# DURST_VT4_V0_3.net
KiCad netlist of a schematic drawn in EAGLE
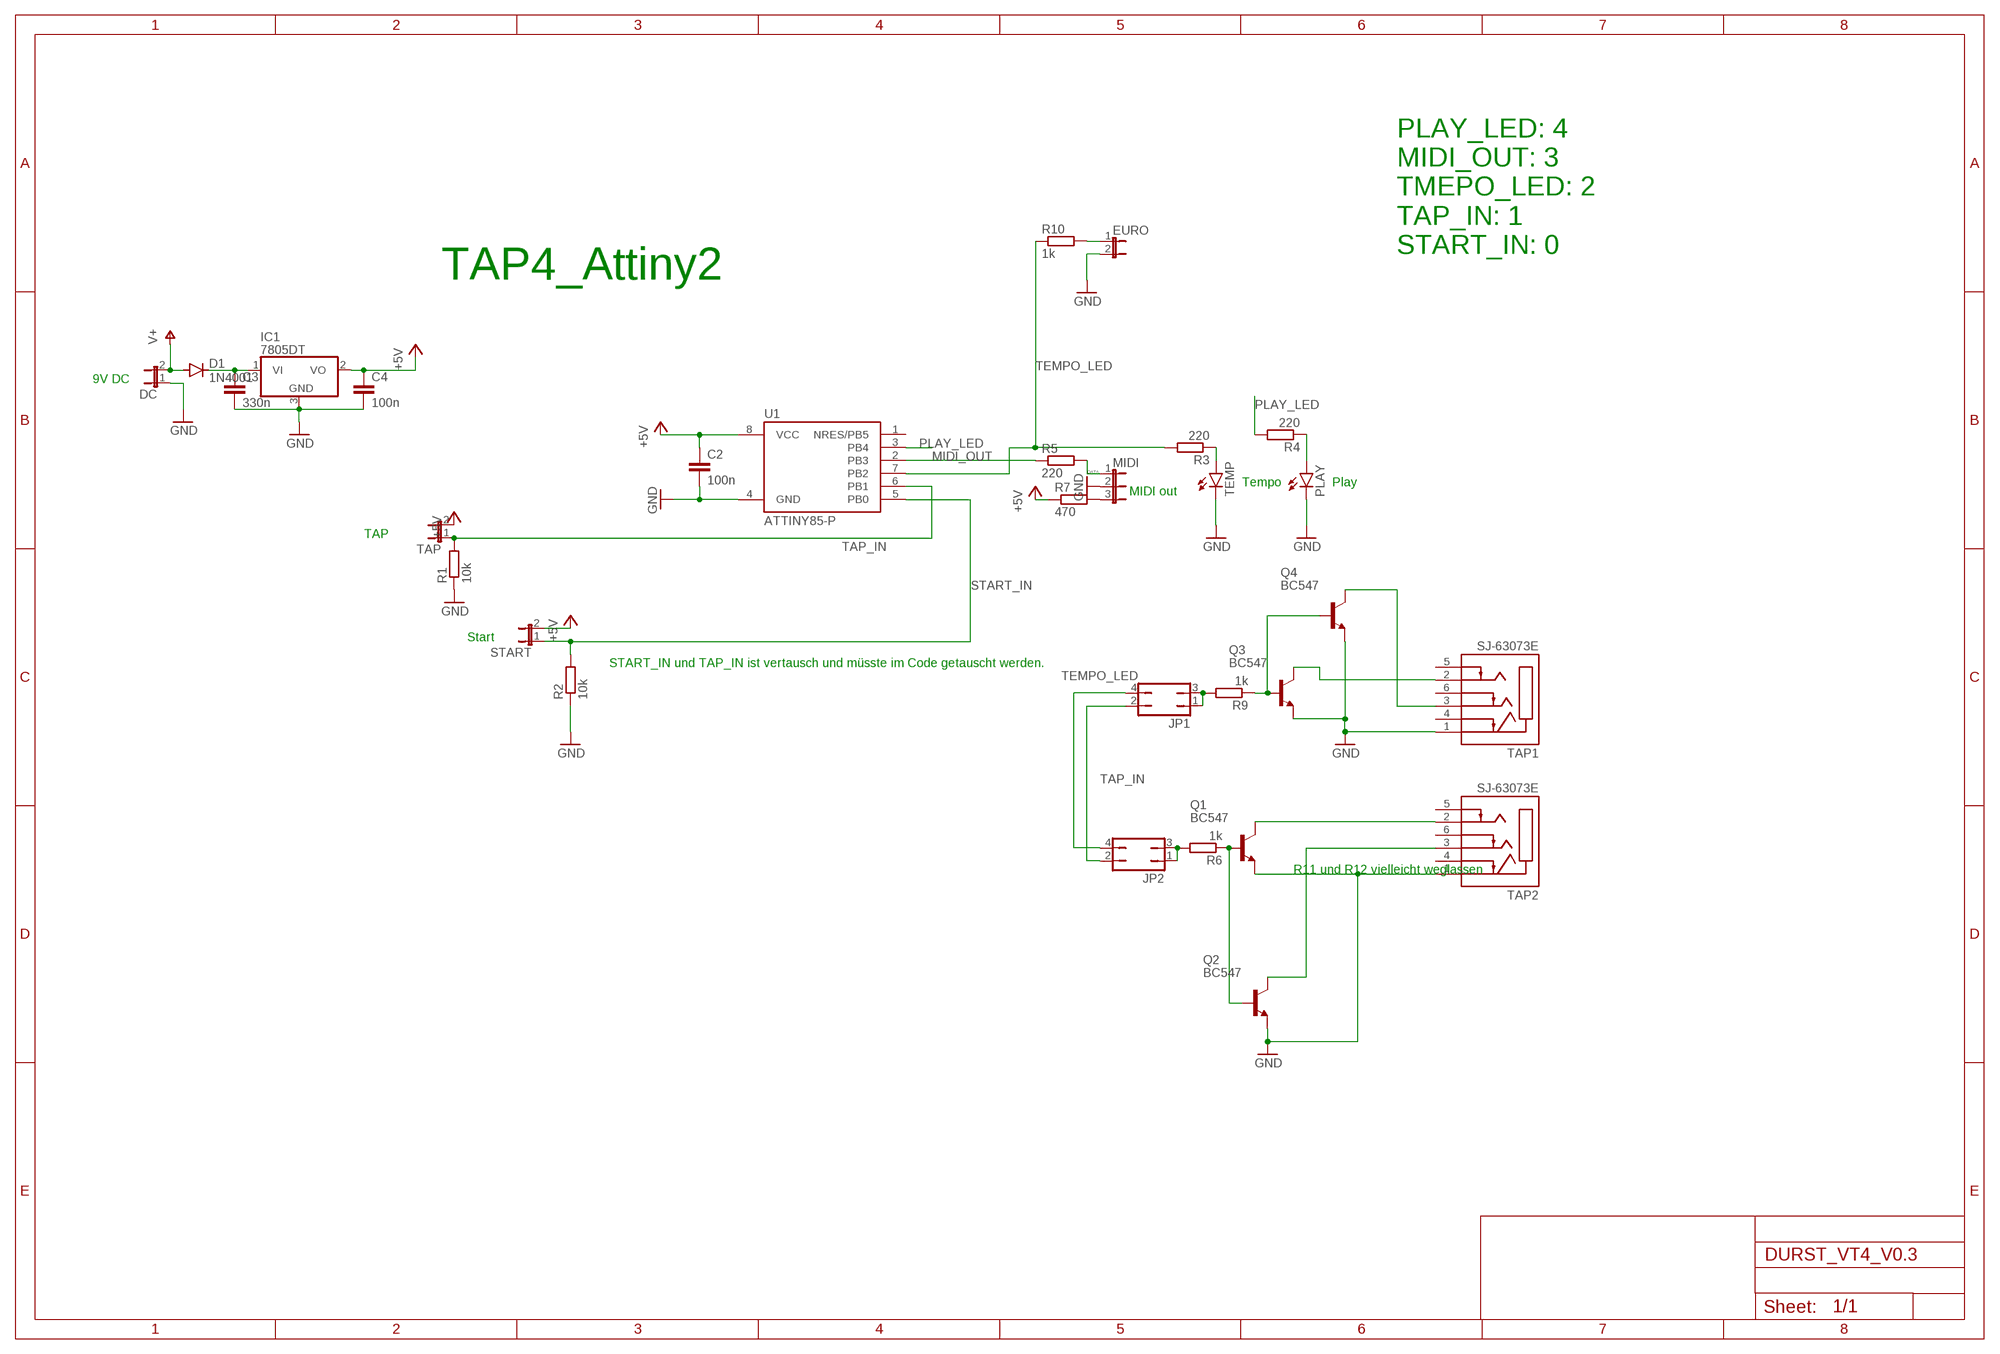
[diagram p0: schematic, sheet 1]

(export (version "E")
  (design (tool "Eeschema 10.0.6"))
  (components
    (comp (ref "C2")
      (value "100n")
      (footprint "eagle-import:C050-024X044")
      (libsource (lib "eagle-import") (part "C-EU050-024X044"))
    )
    (comp (ref "C3")
      (value "330n")
      (footprint "eagle-import:C025-024X044")
      (libsource (lib "eagle-import") (part "C-EU025-024X044"))
    )
    (comp (ref "C4")
      (value "100n")
      (footprint "eagle-import:C025-024X044")
      (libsource (lib "eagle-import") (part "C-EU025-024X044"))
    )
    (comp (ref "D1")
      (value "1N4001")
      (footprint "eagle-import:DO41-10")
      (libsource (lib "eagle-import") (part "1N4004"))
    )
    (comp (ref "DC")
      (value "JP1E")
      (footprint "eagle-import:JP1")
      (libsource (lib "eagle-import") (part "JP1E"))
    )
    (comp (ref "EURO")
      (value "JP1E")
      (footprint "eagle-import:JP1")
      (libsource (lib "eagle-import") (part "JP1E"))
    )
    (comp (ref "IC1")
      (value "7805DT")
      (footprint "eagle-import:TO252")
      (libsource (lib "eagle-import") (part "78DT05"))
    )
    (comp (ref "JP1")
      (value "JP2Q")
      (footprint "eagle-import:JP2Q")
      (libsource (lib "eagle-import") (part "JP2Q"))
    )
    (comp (ref "JP2")
      (value "JP2Q")
      (footprint "eagle-import:JP2Q")
      (libsource (lib "eagle-import") (part "JP2Q"))
    )
    (comp (ref "MIDI")
      (value "JP2E")
      (footprint "eagle-import:JP2")
      (libsource (lib "eagle-import") (part "JP2E"))
    )
    (comp (ref "PLAY")
      (value "LED5MM")
      (footprint "eagle-import:LED5MM")
      (libsource (lib "eagle-import") (part "LED5MM"))
    )
    (comp (ref "Q1")
      (value "BC547")
      (footprint "eagle-import:TO92")
      (libsource (lib "eagle-import") (part "BC547"))
    )
    (comp (ref "Q2")
      (value "BC547")
      (footprint "eagle-import:TO92")
      (libsource (lib "eagle-import") (part "BC547"))
    )
    (comp (ref "Q3")
      (value "BC547")
      (footprint "eagle-import:TO92")
      (libsource (lib "eagle-import") (part "BC547"))
    )
    (comp (ref "Q4")
      (value "BC547")
      (footprint "eagle-import:TO92")
      (libsource (lib "eagle-import") (part "BC547"))
    )
    (comp (ref "R1")
      (value "10k")
      (footprint "eagle-import:0309_10")
      (libsource (lib "eagle-import") (part "R-EU_0309/10"))
    )
    (comp (ref "R2")
      (value "10k")
      (footprint "eagle-import:0309_10")
      (libsource (lib "eagle-import") (part "R-EU_0309/10"))
    )
    (comp (ref "R3")
      (value "220")
      (footprint "eagle-import:0309_10")
      (libsource (lib "eagle-import") (part "R-EU_0309/10"))
    )
    (comp (ref "R4")
      (value "220")
      (footprint "eagle-import:0309_10")
      (libsource (lib "eagle-import") (part "R-EU_0309/10"))
    )
    (comp (ref "R5")
      (value "220")
      (footprint "eagle-import:0309_10")
      (libsource (lib "eagle-import") (part "R-EU_0309/10"))
    )
    (comp (ref "R6")
      (value "1k")
      (footprint "eagle-import:0309_10")
      (libsource (lib "eagle-import") (part "R-EU_0309/10"))
    )
    (comp (ref "R7")
      (value "470")
      (footprint "eagle-import:0309_10")
      (libsource (lib "eagle-import") (part "R-EU_0309/10"))
    )
    (comp (ref "R9")
      (value "1k")
      (footprint "eagle-import:0309_10")
      (libsource (lib "eagle-import") (part "R-EU_0309/10"))
    )
    (comp (ref "R10")
      (value "1k")
      (footprint "eagle-import:0309_10")
      (libsource (lib "eagle-import") (part "R-EU_0309/10"))
    )
    (comp (ref "START")
      (value "JP1E")
      (footprint "eagle-import:JP1")
      (libsource (lib "eagle-import") (part "JP1E"))
    )
    (comp (ref "TAP")
      (value "JP1E")
      (footprint "eagle-import:JP1")
      (libsource (lib "eagle-import") (part "JP1E"))
    )
    (comp (ref "TAP1")
      (value "SJ-63073E")
      (footprint "eagle-import:CUI_SJ-63073E")
      (fields (field (name "MF") "CUI Devices"))
      (libsource (lib "eagle-import") (part "SJ-63073E"))
    )
    (comp (ref "TAP2")
      (value "SJ-63073E")
      (footprint "eagle-import:CUI_SJ-63073E")
      (fields (field (name "MF") "CUI Devices"))
      (libsource (lib "eagle-import") (part "SJ-63073E"))
    )
    (comp (ref "TEMP")
      (value "LED5MM")
      (footprint "eagle-import:LED5MM")
      (libsource (lib "eagle-import") (part "LED5MM"))
    )
    (comp (ref "U1")
      (value "ATTINY85-P")
      (footprint "eagle-import:PDIP08_300MIL")
      (libsource (lib "eagle-import") (part "ATTINY85P-"))
    )
  )
  (nets
    (net (code "1") (name "+5V") (class "Default")
      (node (ref "C2") (pin "1") (pinfunction "1_1") (pintype "passive"))
      (node (ref "C4") (pin "1") (pinfunction "1_1") (pintype "passive"))
      (node (ref "IC1") (pin "2") (pinfunction "VO_2") (pintype "passive"))
      (node (ref "R7") (pin "1") (pinfunction "1_1") (pintype "passive"))
      (node (ref "START") (pin "2") (pinfunction "2_2") (pintype "passive"))
      (node (ref "TAP") (pin "2") (pinfunction "2_2") (pintype "passive"))
      (node (ref "U1") (pin "8") (pinfunction "VCC_8") (pintype "power_in"))
    )
    (net (code "2") (name "/DATA") (class "Default")
      (node (ref "MIDI") (pin "1") (pinfunction "1_1") (pintype "passive"))
      (node (ref "R5") (pin "2") (pinfunction "2_2") (pintype "passive"))
    )
    (net (code "3") (name "/MIDI_OUT") (class "Default")
      (node (ref "R5") (pin "1") (pinfunction "1_1") (pintype "passive"))
      (node (ref "U1") (pin "2") (pinfunction "PB3_2") (pintype "bidirectional"))
    )
    (net (code "4") (name "/PLAY_LED") (class "Default")
      (node (ref "R4") (pin "2") (pinfunction "2_2") (pintype "passive"))
      (node (ref "U1") (pin "3") (pinfunction "PB4_3") (pintype "bidirectional"))
    )
    (net (code "5") (name "/START_IN") (class "Default")
      (node (ref "R2") (pin "2") (pinfunction "2_2") (pintype "passive"))
      (node (ref "START") (pin "1") (pinfunction "1_1") (pintype "passive"))
      (node (ref "U1") (pin "5") (pinfunction "PB0_5") (pintype "bidirectional"))
    )
    (net (code "6") (name "/TAP_IN") (class "Default")
      (node (ref "JP1") (pin "2") (pinfunction "2_2") (pintype "passive"))
      (node (ref "JP2") (pin "2") (pinfunction "2_2") (pintype "passive"))
      (node (ref "R1") (pin "2") (pinfunction "2_2") (pintype "passive"))
      (node (ref "TAP") (pin "1") (pinfunction "1_1") (pintype "passive"))
      (node (ref "U1") (pin "6") (pinfunction "PB1_6") (pintype "bidirectional"))
    )
    (net (code "7") (name "/TEMPO_LED") (class "Default")
      (node (ref "JP1") (pin "4") (pinfunction "4_4") (pintype "passive"))
      (node (ref "JP2") (pin "4") (pinfunction "4_4") (pintype "passive"))
      (node (ref "R10") (pin "1") (pinfunction "1_1") (pintype "passive"))
      (node (ref "R3") (pin "2") (pinfunction "2_2") (pintype "passive"))
      (node (ref "U1") (pin "7") (pinfunction "PB2_7") (pintype "bidirectional"))
    )
    (net (code "8") (name "GND") (class "Default")
      (node (ref "C2") (pin "2") (pinfunction "2_2") (pintype "passive"))
      (node (ref "C3") (pin "2") (pinfunction "2_2") (pintype "passive"))
      (node (ref "C4") (pin "2") (pinfunction "2_2") (pintype "passive"))
      (node (ref "DC") (pin "1") (pinfunction "1_1") (pintype "passive"))
      (node (ref "EURO") (pin "2") (pinfunction "2_2") (pintype "passive"))
      (node (ref "IC1") (pin "3") (pinfunction "GND_3") (pintype "passive"))
      (node (ref "MIDI") (pin "2") (pinfunction "2_2") (pintype "passive"))
      (node (ref "PLAY") (pin "K") (pinfunction "C_K") (pintype "passive"))
      (node (ref "Q1") (pin "1") (pinfunction "E_1") (pintype "passive"))
      (node (ref "Q2") (pin "1") (pinfunction "E_1") (pintype "passive"))
      (node (ref "Q3") (pin "1") (pinfunction "E_1") (pintype "passive"))
      (node (ref "Q4") (pin "1") (pinfunction "E_1") (pintype "passive"))
      (node (ref "R1") (pin "1") (pinfunction "1_1") (pintype "passive"))
      (node (ref "R2") (pin "1") (pinfunction "1_1") (pintype "passive"))
      (node (ref "TAP1") (pin "1") (pinfunction "SLEEVE_1") (pintype "passive"))
      (node (ref "TAP2") (pin "1") (pinfunction "SLEEVE_1") (pintype "passive"))
      (node (ref "TEMP") (pin "K") (pinfunction "C_K") (pintype "passive"))
      (node (ref "U1") (pin "4") (pinfunction "GND_4") (pintype "power_in"))
    )
    (net (code "9") (name "Net-(EURO-Pad1)") (class "Default")
      (node (ref "EURO") (pin "1") (pinfunction "1_1") (pintype "passive"))
      (node (ref "R10") (pin "2") (pinfunction "2_2") (pintype "passive"))
    )
    (net (code "10") (name "Net-(IC1-VI)") (class "Default")
      (node (ref "C3") (pin "1") (pinfunction "1_1") (pintype "passive"))
      (node (ref "D1") (pin "C") (pinfunction "C_C") (pintype "passive"))
      (node (ref "IC1") (pin "1") (pinfunction "VI_1") (pintype "input"))
    )
    (net (code "11") (name "Net-(JP1-Pad1)") (class "Default")
      (node (ref "JP1") (pin "1") (pinfunction "1_1") (pintype "passive"))
      (node (ref "JP1") (pin "3") (pinfunction "3_3") (pintype "passive"))
      (node (ref "R9") (pin "2") (pinfunction "2_2") (pintype "passive"))
    )
    (net (code "12") (name "Net-(JP2-Pad1)") (class "Default")
      (node (ref "JP2") (pin "1") (pinfunction "1_1") (pintype "passive"))
      (node (ref "JP2") (pin "3") (pinfunction "3_3") (pintype "passive"))
      (node (ref "R6") (pin "2") (pinfunction "2_2") (pintype "passive"))
    )
    (net (code "13") (name "Net-(MIDI-Pad3)") (class "Default")
      (node (ref "MIDI") (pin "3") (pinfunction "3_3") (pintype "passive"))
      (node (ref "R7") (pin "2") (pinfunction "2_2") (pintype "passive"))
    )
    (net (code "14") (name "Net-(PLAY-PadA)") (class "Default")
      (node (ref "PLAY") (pin "A") (pinfunction "A_A") (pintype "passive"))
      (node (ref "R4") (pin "1") (pinfunction "1_1") (pintype "passive"))
    )
    (net (code "15") (name "Net-(Q1-B)") (class "Default")
      (node (ref "Q1") (pin "2") (pinfunction "B_2") (pintype "passive"))
      (node (ref "Q2") (pin "2") (pinfunction "B_2") (pintype "passive"))
      (node (ref "R6") (pin "1") (pinfunction "1_1") (pintype "passive"))
    )
    (net (code "16") (name "Net-(Q1-C)") (class "Default")
      (node (ref "Q1") (pin "3") (pinfunction "C_3") (pintype "passive"))
      (node (ref "TAP2") (pin "2") (pinfunction "TIP_2") (pintype "passive"))
    )
    (net (code "17") (name "Net-(Q2-C)") (class "Default")
      (node (ref "Q2") (pin "3") (pinfunction "C_3") (pintype "passive"))
      (node (ref "TAP2") (pin "3") (pinfunction "RING_3") (pintype "passive"))
    )
    (net (code "18") (name "Net-(Q3-B)") (class "Default")
      (node (ref "Q3") (pin "2") (pinfunction "B_2") (pintype "passive"))
      (node (ref "Q4") (pin "2") (pinfunction "B_2") (pintype "passive"))
      (node (ref "R9") (pin "1") (pinfunction "1_1") (pintype "passive"))
    )
    (net (code "19") (name "Net-(Q3-C)") (class "Default")
      (node (ref "Q3") (pin "3") (pinfunction "C_3") (pintype "passive"))
      (node (ref "TAP1") (pin "2") (pinfunction "TIP_2") (pintype "passive"))
    )
    (net (code "20") (name "Net-(Q4-C)") (class "Default")
      (node (ref "Q4") (pin "3") (pinfunction "C_3") (pintype "passive"))
      (node (ref "TAP1") (pin "3") (pinfunction "RING_3") (pintype "passive"))
    )
    (net (code "21") (name "Net-(R3-Pad1)") (class "Default")
      (node (ref "R3") (pin "1") (pinfunction "1_1") (pintype "passive"))
      (node (ref "TEMP") (pin "A") (pinfunction "A_A") (pintype "passive"))
    )
    (net (code "22") (name "V+") (class "Default")
      (node (ref "D1") (pin "A") (pinfunction "A_A") (pintype "passive"))
      (node (ref "DC") (pin "2") (pinfunction "2_2") (pintype "passive"))
    )
    (net (code "23") (name "unconnected-(TAP1-RING_SWITCH-Pad6)") (class "Default")
      (node (ref "TAP1") (pin "6") (pinfunction "RING_SWITCH_6") (pintype "passive"))
    )
    (net (code "24") (name "unconnected-(TAP1-SLEEVE_SWITCH-Pad4)") (class "Default")
      (node (ref "TAP1") (pin "4") (pinfunction "SLEEVE_SWITCH_4") (pintype "passive"))
    )
    (net (code "25") (name "unconnected-(TAP1-TIP_SWITCH-Pad5)") (class "Default")
      (node (ref "TAP1") (pin "5") (pinfunction "TIP_SWITCH_5") (pintype "passive"))
    )
    (net (code "26") (name "unconnected-(TAP2-RING_SWITCH-Pad6)") (class "Default")
      (node (ref "TAP2") (pin "6") (pinfunction "RING_SWITCH_6") (pintype "passive"))
    )
    (net (code "27") (name "unconnected-(TAP2-SLEEVE_SWITCH-Pad4)") (class "Default")
      (node (ref "TAP2") (pin "4") (pinfunction "SLEEVE_SWITCH_4") (pintype "passive"))
    )
    (net (code "28") (name "unconnected-(TAP2-TIP_SWITCH-Pad5)") (class "Default")
      (node (ref "TAP2") (pin "5") (pinfunction "TIP_SWITCH_5") (pintype "passive"))
    )
    (net (code "29") (name "unconnected-(U1-NRES{slash}PB5-Pad1)") (class "Default")
      (node (ref "U1") (pin "1") (pinfunction "NRES/PB5_1") (pintype "bidirectional"))
    )
  )
)
